# RTCE.net
KiCad netlist of a schematic drawn in Altium Designer
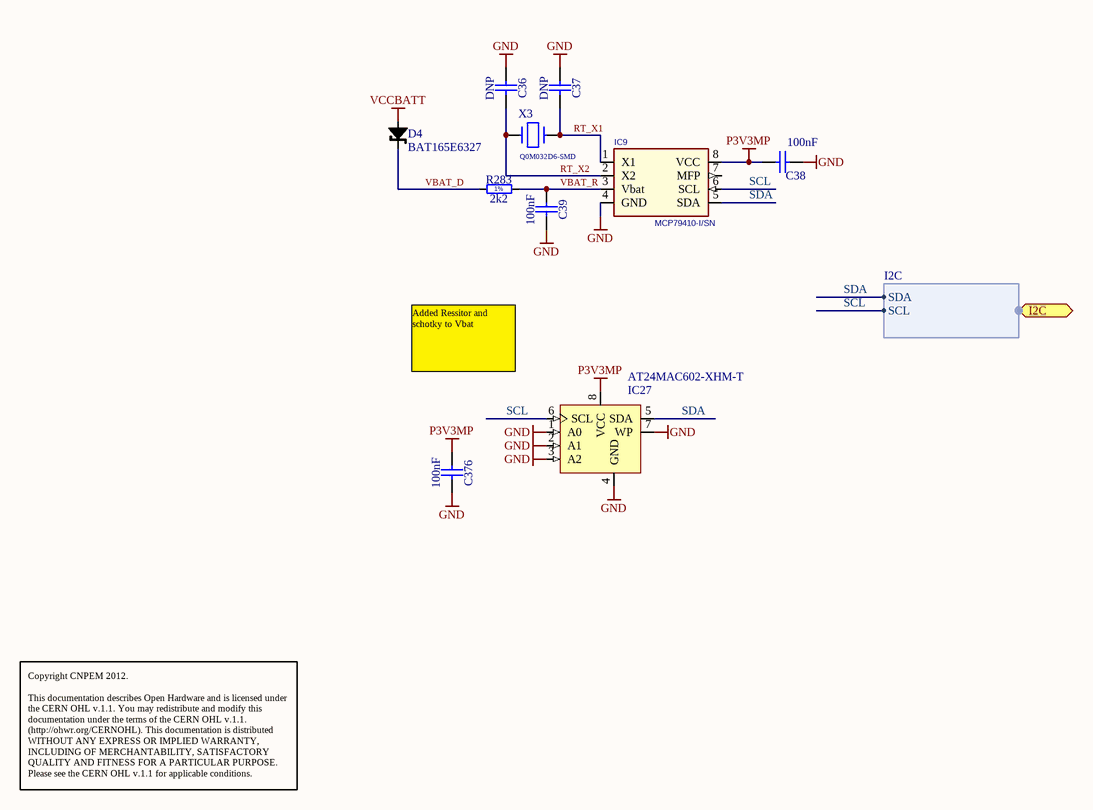
[diagram p0: RTCE.SchDoc]

(export (version "E")
  (design (tool "Eeschema 10.0.6"))
  (components
    (comp (ref "C36")
      (value "DNP")
      (footprint "CAPC1005X55N")
      (description "Non-polarised capacitor")
      (fields
        (field (name "PART NUMBER") "CC0402_15PF_50V_5%_NP0")
        (field (name "VOLTAGE") "50V")
        (field (name "AUTHOR") "CERN DEM JLC")
      )
      (libsource (lib "Capacitors") (part "Capacitor - non polarized"))
    )
    (comp (ref "C37")
      (value "DNP")
      (footprint "CAPC1005X55N")
      (description "Non-polarised capacitor")
      (fields
        (field (name "PART NUMBER") "CC0402_15PF_50V_5%_NP0")
        (field (name "VOLTAGE") "50V")
        (field (name "AUTHOR") "CERN DEM JLC")
      )
      (libsource (lib "Capacitors") (part "Capacitor - non polarized"))
    )
    (comp (ref "C38")
      (value "100nF")
      (footprint "CAPC0603X33N")
      (description "Non-polarised capacitor")
      (fields
        (field (name "PART NUMBER") "CC0201_100NF_6.3V_10%_X5R")
        (field (name "VOLTAGE") "6.3V")
        (field (name "AUTHOR") "CERN DEM JLC")
      )
      (libsource (lib "Capacitors") (part "Capacitor - non polarized"))
    )
    (comp (ref "C39")
      (value "100nF")
      (footprint "CAPC0603X33N")
      (description "Non-polarised capacitor")
      (fields
        (field (name "PART NUMBER") "CC0201_100NF_6.3V_10%_X5R")
        (field (name "VOLTAGE") "6.3V")
        (field (name "AUTHOR") "CERN DEM JLC")
      )
      (libsource (lib "Capacitors") (part "Capacitor - non polarized"))
    )
    (comp (ref "C376")
      (value "100nF")
      (footprint "CAPC0603X33N")
      (description "Non-polarised capacitor")
      (fields
        (field (name "PART NUMBER") "CC0201_100NF_6.3V_10%_X5R")
        (field (name "VOLTAGE") "6.3V")
        (field (name "AUTHOR") "CERN DEM JLC")
      )
      (libsource (lib "Capacitors") (part "Capacitor - non polarized"))
    )
    (comp (ref "D4")
      (value "BAT165E6327")
      (footprint "SOD323")
      (description "500mA, 40V, Shottky Diode")
      (libsource (lib "LIBRARY_SCH") (part "D_BAT165"))
    )
    (comp (ref "IC9")
      (value "MCP79410-I/SN")
      (footprint "SO-8")
      (description "RTC with 1k EEPROM and RAM")
      (libsource (lib "LIBRARY_SCH") (part "RTC_MCP79410"))
    )
    (comp (ref "IC27")
      (value "AT24MAC602-XHM-T")
      (footprint "TSSOP-8")
      (description "Serial 2K EEPROM+ 48bit MAC")
      (libsource (lib "LIBRARY_SCH") (part "MEM_24MAC602"))
    )
    (comp (ref "R283")
      (value "2k2")
      (footprint "RESC1005X40N")
      (description "Resistor - 1%")
      (fields
        (field (name "PART NUMBER") "R0402_2K2_1%_0.0625W_100PPM")
        (field (name "POWER") "0.0625W")
        (field (name "AUTHOR") "CERN DEM JLC")
      )
      (libsource (lib "Resistors") (part "Resistor - 1%"))
    )
    (comp (ref "X3")
      (value "Q0M032D6-SMD")
      (footprint "crystal_85SMX")
      (description "Crystal oscillator 32k (Maritex)")
      (libsource (lib "LIBRARY_SCH") (part "X_CRYSTAL_32k_SMD"))
    )
  )
  (nets
    (net (code "2") (name "/RT_X1") (class "Default")
      (node (ref "C37") (pin "2") (pinfunction "2_2") (pintype "passive"))
      (node (ref "IC9") (pin "1") (pinfunction "X1_1") (pintype "passive"))
      (node (ref "X3") (pin "1") (pinfunction "1_1") (pintype "passive"))
    )
    (net (code "3") (name "/RT_X2") (class "Default")
      (node (ref "C36") (pin "2") (pinfunction "2_2") (pintype "passive"))
      (node (ref "IC9") (pin "2") (pinfunction "X2_2") (pintype "passive"))
      (node (ref "X3") (pin "4") (pinfunction "4_4") (pintype "passive"))
    )
    (net (code "4") (name "/SCL") (class "Default")
      (node (ref "IC27") (pin "6") (pinfunction "SCL_6") (pintype "input"))
      (node (ref "IC9") (pin "6") (pinfunction "SCL_6") (pintype "input"))
    )
    (net (code "5") (name "/SDA") (class "Default")
      (node (ref "IC27") (pin "5") (pinfunction "SDA_5") (pintype "bidirectional"))
      (node (ref "IC9") (pin "5") (pinfunction "SDA_5") (pintype "bidirectional"))
    )
    (net (code "6") (name "/VBAT_D") (class "Default")
      (node (ref "D4") (pin "K") (pinfunction "K_K") (pintype "passive"))
      (node (ref "R283") (pin "1") (pinfunction "1_1") (pintype "passive"))
    )
    (net (code "7") (name "/VBAT_R") (class "Default")
      (node (ref "C39") (pin "1") (pinfunction "1_1") (pintype "passive"))
      (node (ref "IC9") (pin "3") (pinfunction "Vbat_3") (pintype "power_in"))
      (node (ref "R283") (pin "2") (pinfunction "2_2") (pintype "passive"))
    )
    (net (code "9") (name "GND") (class "Default")
      (node (ref "C36") (pin "1") (pinfunction "1_1") (pintype "passive"))
      (node (ref "C37") (pin "1") (pinfunction "1_1") (pintype "passive"))
      (node (ref "C376") (pin "2") (pinfunction "2_2") (pintype "passive"))
      (node (ref "C38") (pin "2") (pinfunction "2_2") (pintype "passive"))
      (node (ref "C39") (pin "2") (pinfunction "2_2") (pintype "passive"))
      (node (ref "IC27") (pin "1") (pinfunction "A0_1") (pintype "input"))
      (node (ref "IC27") (pin "2") (pinfunction "A1_2") (pintype "input"))
      (node (ref "IC27") (pin "3") (pinfunction "A2_3") (pintype "input"))
      (node (ref "IC27") (pin "4") (pinfunction "GND_4") (pintype "power_in"))
      (node (ref "IC27") (pin "7") (pinfunction "WP_7") (pintype "passive"))
      (node (ref "IC9") (pin "4") (pinfunction "GND_4") (pintype "power_in"))
    )
    (net (code "10") (name "P3V3MP") (class "Default")
      (node (ref "C376") (pin "1") (pinfunction "1_1") (pintype "passive"))
      (node (ref "C38") (pin "1") (pinfunction "1_1") (pintype "passive"))
      (node (ref "IC27") (pin "8") (pinfunction "VCC_8") (pintype "power_in"))
      (node (ref "IC9") (pin "8") (pinfunction "VCC_8") (pintype "power_in"))
    )
    (net (code "11") (name "VCCBATT") (class "Default")
      (node (ref "D4") (pin "A") (pinfunction "A_A") (pintype "passive"))
    )
    (net (code "12") (name "unconnected-(IC9-MFP-Pad7)") (class "Default")
      (node (ref "IC9") (pin "7") (pinfunction "MFP_7") (pintype "output"))
    )
  )
)
